# 2_STM32_Power.net
KiCad netlist of a schematic drawn in Altium Designer
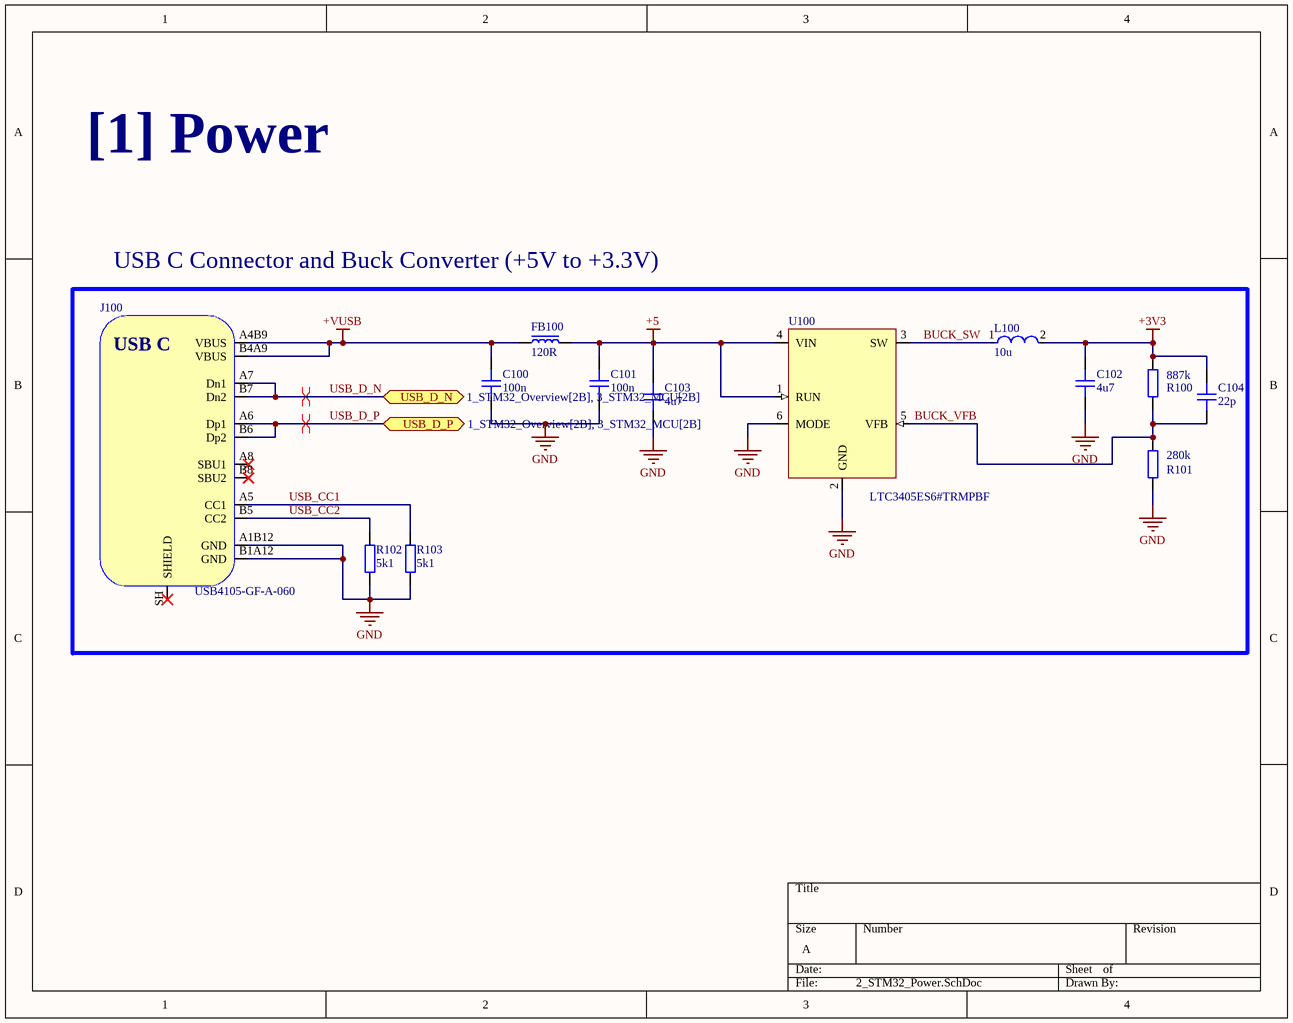
[diagram p0: 2_STM32_Power.SchDoc]

(export (version "E")
  (design (tool "Eeschema 10.0.6"))
  (components
    (comp (ref "C100")
      (value "100n")
      (footprint "CAP_0603")
      (description "Capacitor SMD 0603")
      (libsource (lib "Schematic-Lib-PhilsLab") (part "CAP_0603"))
    )
    (comp (ref "C101")
      (value "100n")
      (footprint "CAP_0603")
      (description "Capacitor SMD 0603")
      (libsource (lib "Schematic-Lib-PhilsLab") (part "CAP_0603"))
    )
    (comp (ref "C102")
      (value "4u7")
      (footprint "CAP_0603")
      (description "Capacitor SMD 0603")
      (libsource (lib "Schematic-Lib-PhilsLab") (part "CAP_0603"))
    )
    (comp (ref "C103")
      (value "4u7")
      (footprint "CAP_0603")
      (description "Capacitor SMD 0603")
      (libsource (lib "Schematic-Lib-PhilsLab") (part "CAP_0603"))
    )
    (comp (ref "C104")
      (value "22p")
      (footprint "CAP_0603")
      (description "Capacitor SMD 0603")
      (libsource (lib "Schematic-Lib-PhilsLab") (part "CAP_0603"))
    )
    (comp (ref "FB100")
      (value "120R")
      (footprint "FB_0603")
      (description "Ferrite Bead SMD 0603")
      (libsource (lib "Schematic-Lib-PhilsLab") (part "FB_0603"))
    )
    (comp (ref "J100")
      (value "USB4105-GF-A-060")
      (footprint "USB4105-GF-A-060")
      (description "USB Connector Type C SMT 12 Pin")
      (fields (field (name "MANUFACTURER") "GCT"))
      (libsource (lib "Schematic-Lib-PhilsLab") (part "USB4105-GF-A-060"))
    )
    (comp (ref "L100")
      (value "10u")
      (footprint "FP-NRH2412-MFG")
      (description "Shielded Wirewound Inductor 10uH 20% 0.51A 0.72Ω SMD")
      (fields (field (name "TOLERANCE") "20%"))
      (libsource (lib "Altium Content Vault") (part "725321dda6339637d4d059423bc1c3c"))
    )
    (comp (ref "R100")
      (value "887k")
      (footprint "RES_0603")
      (description "Resistor SMD 0603")
      (fields (field (name "SOURCE") "Schematic-Lib-PhilsLab.SchLib"))
      (libsource (lib "Industrial University of Ho Chi Minh City") (part "RES_5931"))
    )
    (comp (ref "R101")
      (value "280k")
      (footprint "RES_0603")
      (description "Resistor SMD 0603")
      (fields (field (name "SOURCE") "Schematic-Lib-PhilsLab.SchLib"))
      (libsource (lib "Industrial University of Ho Chi Minh City") (part "RES_5931"))
    )
    (comp (ref "R102")
      (value "5k1")
      (footprint "RES_0603")
      (description "Resistor SMD 0603")
      (libsource (lib "Schematic-Lib-PhilsLab") (part "RES_0603"))
    )
    (comp (ref "R103")
      (value "5k1")
      (footprint "RES_0603")
      (description "Resistor SMD 0603")
      (libsource (lib "Schematic-Lib-PhilsLab") (part "RES_0603"))
    )
    (comp (ref "U100")
      (value "LTC3405ES6#TRMPBF")
      (footprint "SOT-23-6")
      (description "1.5MHz, 300mA\r\nSynchronous Step-Down\r\nRegulator in ThinSOT")
      (fields (field (name "MANUFACTURER") "Analog Devices"))
      (libsource (lib "Schematic-Lib-PhilsLab") (part "LTC3405ES6#TRMPBF"))
    )
  )
  (nets
    (net (code "1") (name "+3V3") (class "Default")
      (node (ref "C102") (pin "2") (pinfunction "2_2") (pintype "passive"))
      (node (ref "C104") (pin "2") (pinfunction "2_2") (pintype "passive"))
      (node (ref "L100") (pin "2") (pinfunction "2_2") (pintype "passive"))
      (node (ref "R100") (pin "2") (pinfunction "2_2") (pintype "passive"))
    )
    (net (code "2") (name "+5") (class "Default")
      (node (ref "C101") (pin "2") (pinfunction "2_2") (pintype "passive"))
      (node (ref "C103") (pin "2") (pinfunction "2_2") (pintype "passive"))
      (node (ref "FB100") (pin "2") (pinfunction "2_2") (pintype "passive"))
      (node (ref "U100") (pin "1") (pinfunction "RUN_1") (pintype "input"))
      (node (ref "U100") (pin "4") (pinfunction "VIN_4") (pintype "power_in"))
    )
    (net (code "3") (name "+VUSB") (class "Default")
      (node (ref "C100") (pin "2") (pinfunction "2_2") (pintype "passive"))
      (node (ref "FB100") (pin "1") (pinfunction "1_1") (pintype "passive"))
      (node (ref "J100") (pin "A4B9") (pinfunction "VBUS_A4B9") (pintype "passive"))
      (node (ref "J100") (pin "B4A9") (pinfunction "VBUS_B4A9") (pintype "passive"))
    )
    (net (code "4") (name "/BUCK_SW") (class "Default")
      (node (ref "L100") (pin "1") (pinfunction "1_1") (pintype "passive"))
      (node (ref "U100") (pin "3") (pinfunction "SW_3") (pintype "power_in"))
    )
    (net (code "5") (name "/BUCK_VFB") (class "Default")
      (node (ref "C104") (pin "1") (pinfunction "1_1") (pintype "passive"))
      (node (ref "R100") (pin "1") (pinfunction "1_1") (pintype "passive"))
      (node (ref "R101") (pin "2") (pinfunction "2_2") (pintype "passive"))
      (node (ref "U100") (pin "5") (pinfunction "VFB_5") (pintype "input"))
    )
    (net (code "6") (name "/USB_CC1") (class "Default")
      (node (ref "J100") (pin "A5") (pinfunction "CC1_A5") (pintype "passive"))
      (node (ref "R103") (pin "2") (pinfunction "2_2") (pintype "passive"))
    )
    (net (code "7") (name "/USB_CC2") (class "Default")
      (node (ref "J100") (pin "B5") (pinfunction "CC2_B5") (pintype "passive"))
      (node (ref "R102") (pin "2") (pinfunction "2_2") (pintype "passive"))
    )
    (net (code "8") (name "/USB_D_N") (class "Default")
      (node (ref "J100") (pin "A7") (pinfunction "Dn1_A7") (pintype "passive"))
      (node (ref "J100") (pin "B7") (pinfunction "Dn2_B7") (pintype "passive"))
    )
    (net (code "9") (name "/USB_D_P") (class "Default")
      (node (ref "J100") (pin "A6") (pinfunction "Dp1_A6") (pintype "passive"))
      (node (ref "J100") (pin "B6") (pinfunction "Dp2_B6") (pintype "passive"))
    )
    (net (code "10") (name "GND") (class "Default")
      (node (ref "C100") (pin "1") (pinfunction "1_1") (pintype "passive"))
      (node (ref "C101") (pin "1") (pinfunction "1_1") (pintype "passive"))
      (node (ref "C102") (pin "1") (pinfunction "1_1") (pintype "passive"))
      (node (ref "C103") (pin "1") (pinfunction "1_1") (pintype "passive"))
      (node (ref "J100") (pin "A1B12") (pinfunction "GND_A1B12") (pintype "passive"))
      (node (ref "J100") (pin "B1A12") (pinfunction "GND_B1A12") (pintype "passive"))
      (node (ref "R101") (pin "1") (pinfunction "1_1") (pintype "passive"))
      (node (ref "R102") (pin "1") (pinfunction "1_1") (pintype "passive"))
      (node (ref "R103") (pin "1") (pinfunction "1_1") (pintype "passive"))
      (node (ref "U100") (pin "2") (pinfunction "GND_2") (pintype "power_in"))
      (node (ref "U100") (pin "6") (pinfunction "MODE_6") (pintype "passive"))
    )
    (net (code "11") (name "unconnected-(J100-SBU1-PadA8)") (class "Default")
      (node (ref "J100") (pin "A8") (pinfunction "SBU1_A8") (pintype "passive+no_connect"))
    )
    (net (code "12") (name "unconnected-(J100-SBU2-PadB8)") (class "Default")
      (node (ref "J100") (pin "B8") (pinfunction "SBU2_B8") (pintype "passive+no_connect"))
    )
    (net (code "13") (name "unconnected-(J100-SHIELD-PadSH)") (class "Default")
      (node (ref "J100") (pin "SH") (pinfunction "SHIELD_SH") (pintype "passive+no_connect"))
    )
  )
)
